# max1811_ladowarka_prosta.net
KiCad netlist of a schematic drawn in EAGLE
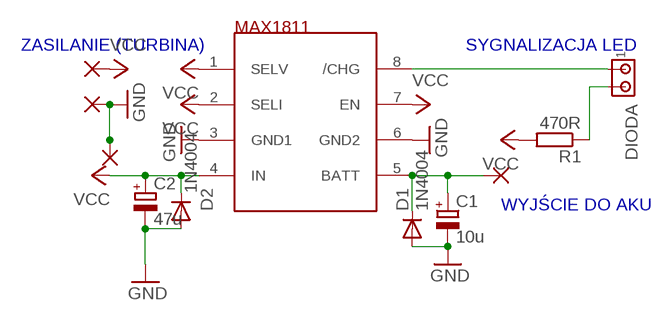
[diagram p0: schematic, sheet 1]

(export (version "E")
  (design (tool "Eeschema 10.0.6"))
  (components
    (comp (ref "BATERIA")
      (value "1,6/0,9")
      (footprint "eagle-import:1,6_0,9")
      (libsource (lib "eagle-import") (part "1,6/0,9"))
    )
    (comp (ref "C1")
      (value "10u")
      (footprint "eagle-import:E2,5-6")
      (libsource (lib "eagle-import") (part "CPOL-EUE2.5-6"))
    )
    (comp (ref "C2")
      (value "47u")
      (footprint "eagle-import:E2,5-6")
      (libsource (lib "eagle-import") (part "CPOL-EUE2.5-6"))
    )
    (comp (ref "D1")
      (value "1N4004")
      (footprint "eagle-import:DO41-10")
      (libsource (lib "eagle-import") (part "1N4004"))
    )
    (comp (ref "D2")
      (value "1N4004")
      (footprint "eagle-import:DO41-10")
      (libsource (lib "eagle-import") (part "1N4004"))
    )
    (comp (ref "DIODA")
      (value "MTA02-100")
      (footprint "eagle-import:10X02MTA")
      (libsource (lib "eagle-import") (part "MTA02-100"))
    )
    (comp (ref "PAD2")
      (value "1,6/0,9")
      (footprint "eagle-import:1,6_0,9")
      (libsource (lib "eagle-import") (part "1,6/0,9"))
    )
    (comp (ref "PAD4")
      (value "1,6/0,9")
      (footprint "eagle-import:1,6_0,9")
      (libsource (lib "eagle-import") (part "1,6/0,9"))
    )
    (comp (ref "R1")
      (value "470R")
      (footprint "eagle-import:R0805")
      (libsource (lib "eagle-import") (part "R-EU_R0805"))
    )
    (comp (ref "U$1")
      (value "MAX1811")
      (footprint "eagle-import:SO-08")
      (libsource (lib "eagle-import") (part "MAX1811"))
    )
    (comp (ref "WEJ")
      (value "1,6/0,9")
      (footprint "eagle-import:1,6_0,9")
      (libsource (lib "eagle-import") (part "1,6/0,9"))
    )
  )
  (nets
    (net (code "1") (name "GND") (class "Default")
      (node (ref "C1") (pin "-") (pinfunction "-_-") (pintype "passive"))
      (node (ref "C2") (pin "-") (pinfunction "-_-") (pintype "passive"))
      (node (ref "D1") (pin "A") (pinfunction "A_A") (pintype "passive"))
      (node (ref "D2") (pin "A") (pinfunction "A_A") (pintype "passive"))
      (node (ref "PAD2") (pin "1") (pinfunction "P_1") (pintype "passive"))
      (node (ref "PAD4") (pin "1") (pinfunction "P_1") (pintype "passive"))
      (node (ref "U$1") (pin "3") (pinfunction "GND1_3") (pintype "bidirectional"))
      (node (ref "U$1") (pin "6") (pinfunction "GND2_6") (pintype "bidirectional"))
    )
    (net (code "2") (name "Net-(BATERIA-P)") (class "Default")
      (node (ref "BATERIA") (pin "1") (pinfunction "P_1") (pintype "passive"))
      (node (ref "C1") (pin "+") (pinfunction "+_+") (pintype "passive"))
      (node (ref "D1") (pin "C") (pinfunction "C_C") (pintype "passive"))
      (node (ref "U$1") (pin "5") (pinfunction "BATT_5") (pintype "bidirectional"))
    )
    (net (code "3") (name "Net-(DIODA-Pad2)") (class "Default")
      (node (ref "DIODA") (pin "2") (pinfunction "2_2") (pintype "passive"))
      (node (ref "R1") (pin "1") (pinfunction "1_1") (pintype "passive"))
    )
    (net (code "4") (name "Net-(U$1-{slash}CHG)") (class "Default")
      (node (ref "DIODA") (pin "1") (pinfunction "1_1") (pintype "passive"))
      (node (ref "U$1") (pin "8") (pinfunction "/CHG_8") (pintype "bidirectional"))
    )
    (net (code "5") (name "VCC") (class "Default")
      (node (ref "C2") (pin "+") (pinfunction "+_+") (pintype "passive"))
      (node (ref "D2") (pin "C") (pinfunction "C_C") (pintype "passive"))
      (node (ref "R1") (pin "2") (pinfunction "2_2") (pintype "passive"))
      (node (ref "U$1") (pin "1") (pinfunction "SELV_1") (pintype "bidirectional"))
      (node (ref "U$1") (pin "2") (pinfunction "SELI_2") (pintype "bidirectional"))
      (node (ref "U$1") (pin "4") (pinfunction "IN_4") (pintype "bidirectional"))
      (node (ref "U$1") (pin "7") (pinfunction "EN_7") (pintype "bidirectional"))
      (node (ref "WEJ") (pin "1") (pinfunction "P_1") (pintype "passive"))
    )
  )
)
